# design.net
KiCad netlist of a schematic drawn in Altium Designer
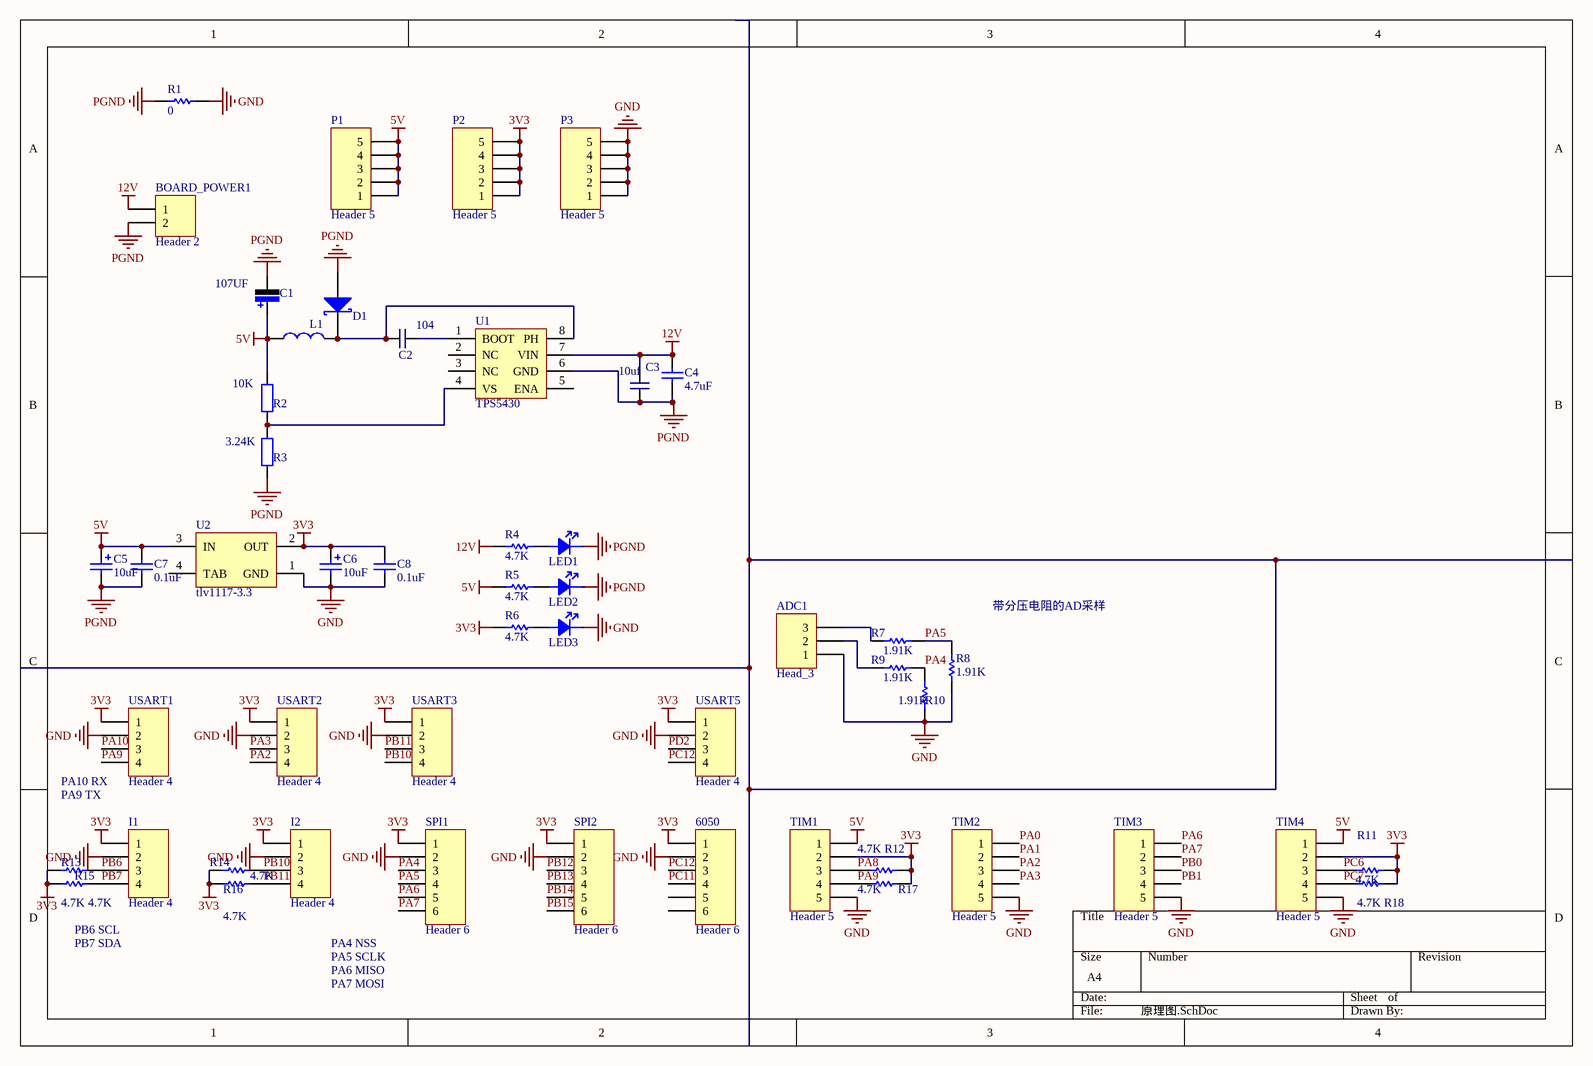
[diagram p0: 原理图.SchDoc]

(export (version "E")
  (design (tool "Eeschema 10.0.6"))
  (components
    (comp (ref "6050")
      (value "Header 6")
      (footprint "HDR1X6- duplicate")
      (description "接插件")
      (fields (field (name "PUBLISHER") "Altium Limited"))
      (libsource (lib "MySchlib") (part "Header 6"))
    )
    (comp (ref "ADC1") (value "Head_3") (footprint "HDR1X3") (libsource (lib "MySchlib") (part "Head_3")))
    (comp (ref "BOARD_POWER1")
      (value "Header 2")
      (footprint "Green_2P")
      (description "Header, 2-Pin")
      (fields (field (name "PUBLISHER") "Altium Limited"))
      (libsource (lib "K60-mainboard-v3.1") (part "Header 2"))
    )
    (comp (ref "C1")
      (value "107UF")
      (footprint "6032C  TA")
      (description "钽电容")
      (libsource (lib "MySchlib") (part "Cap_2"))
    )
    (comp (ref "C2") (value "104") (footprint "0603- C") (libsource (lib "MySchlib") (part "Cap")))
    (comp (ref "C3") (value "10uf") (footprint "0805C") (libsource (lib "MySchlib") (part "Cap")))
    (comp (ref "C4")
      (value "4.7uF")
      (footprint "CAP-MLCC-0603")
      (description "Capacitor")
      (fields (field (name "Comment") "Cap") (field (name "PUBLISHER") "Altium Limited"))
      (libsource (lib "K60-mainboard-v3.1") (part "Cap"))
    )
    (comp (ref "C5")
      (value "10uF")
      (footprint "6032C")
      (description "Polarized Capacitor (Radial)")
      (fields (field (name "Comment") "Cap Pol1") (field (name "PUBLISHER") "Altium Limited"))
      (libsource (lib "K60-mainboard-v3.1") (part "Cap Pol1"))
    )
    (comp (ref "C6")
      (value "10uF")
      (footprint "6032C")
      (description "Polarized Capacitor (Radial)")
      (fields (field (name "Comment") "Cap Pol1") (field (name "PUBLISHER") "Altium Limited"))
      (libsource (lib "K60-mainboard-v3.1") (part "Cap Pol1"))
    )
    (comp (ref "C7")
      (value "0.1uF")
      (footprint "CAP-MLCC-0603")
      (description "Capacitor")
      (fields (field (name "Comment") "Cap") (field (name "PUBLISHER") "Altium Limited"))
      (libsource (lib "K60-mainboard-v3.1") (part "Cap"))
    )
    (comp (ref "C8")
      (value "0.1uF")
      (footprint "CAP-MLCC-0603")
      (description "Capacitor")
      (fields (field (name "Comment") "Cap") (field (name "PUBLISHER") "Altium Limited"))
      (libsource (lib "K60-mainboard-v3.1") (part "Cap"))
    )
    (comp (ref "D1") (value "D") (footprint "D RS1M") (libsource (lib "MySchlib") (part "D")))
    (comp (ref "I1")
      (value "Header 4")
      (footprint "HDR1X4")
      (description "Header, 4-Pin")
      (fields (field (name "PUBLISHER") "Altium Limited"))
      (libsource (lib "K60-mainboard-v3.1") (part "Header 4"))
    )
    (comp (ref "I2")
      (value "Header 4")
      (footprint "HDR1X4")
      (description "Header, 4-Pin")
      (fields (field (name "PUBLISHER") "Altium Limited"))
      (libsource (lib "K60-mainboard-v3.1") (part "Header 4"))
    )
    (comp (ref "L1")
      (value "L")
      (footprint "CD_54")
      (description "电感")
      (libsource (lib "MySchlib") (part "L"))
    )
    (comp (ref "LED1")
      (value "lED")
      (footprint "0805D")
      (description "LED")
      (libsource (lib "K60-mainboard-v3.1") (part "00-D-LED"))
    )
    (comp (ref "LED2")
      (value "lED")
      (footprint "0805D")
      (description "LED")
      (libsource (lib "K60-mainboard-v3.1") (part "00-D-LED"))
    )
    (comp (ref "LED3")
      (value "lED")
      (footprint "0805D")
      (description "LED")
      (libsource (lib "K60-mainboard-v3.1") (part "00-D-LED"))
    )
    (comp (ref "P1")
      (value "Header 5")
      (footprint "HDR1X5")
      (description "Header, 5-Pin")
      (fields (field (name "PUBLISHER") "Altium Limited"))
      (libsource (lib "K60-mainboard-v3.1") (part "Header 5"))
    )
    (comp (ref "P2")
      (value "Header 5")
      (footprint "HDR1X5")
      (description "Header, 5-Pin")
      (fields (field (name "PUBLISHER") "Altium Limited"))
      (libsource (lib "K60-mainboard-v3.1") (part "Header 5"))
    )
    (comp (ref "P3")
      (value "Header 5")
      (footprint "HDR1X5")
      (description "Header, 5-Pin")
      (fields (field (name "PUBLISHER") "Altium Limited"))
      (libsource (lib "K60-mainboard-v3.1") (part "Header 5"))
    )
    (comp (ref "R1")
      (value "0")
      (footprint "RES-0603")
      (description "Resistor")
      (fields (field (name "Comment") "Res1") (field (name "PUBLISHER") "Altium Limited"))
      (libsource (lib "K60-mainboard-v3.1") (part "Res1"))
    )
    (comp (ref "R2") (value "10K") (footprint "0603-R") (libsource (lib "MySchlib") (part "R")))
    (comp (ref "R3") (value "3.24K") (footprint "0603-R") (libsource (lib "") (part "R_1")))
    (comp (ref "R4")
      (value "4.7K")
      (footprint "RES-0603")
      (description "Resistor")
      (fields (field (name "Comment") "Res1") (field (name "PUBLISHER") "Altium Limited"))
      (libsource (lib "K60-mainboard-v3.1") (part "Res1"))
    )
    (comp (ref "R5")
      (value "4.7K")
      (footprint "RES-0603")
      (description "Resistor")
      (fields (field (name "Comment") "Res1") (field (name "PUBLISHER") "Altium Limited"))
      (libsource (lib "K60-mainboard-v3.1") (part "Res1"))
    )
    (comp (ref "R6")
      (value "4.7K")
      (footprint "RES-0603")
      (description "Resistor")
      (fields (field (name "Comment") "Res1") (field (name "PUBLISHER") "Altium Limited"))
      (libsource (lib "K60-mainboard-v3.1") (part "Res1"))
    )
    (comp (ref "R7")
      (value "1.91K")
      (footprint "RES-0603")
      (description "Resistor")
      (fields (field (name "Comment") "Res1") (field (name "PUBLISHER") "Altium Limited"))
      (libsource (lib "K60-mainboard-v3.1") (part "Res1"))
    )
    (comp (ref "R8")
      (value "1.91K")
      (footprint "RES-0603")
      (description "Resistor")
      (fields (field (name "Comment") "Res1") (field (name "PUBLISHER") "Altium Limited"))
      (libsource (lib "K60-mainboard-v3.1") (part "Res1"))
    )
    (comp (ref "R9")
      (value "1.91K")
      (footprint "RES-0603")
      (description "Resistor")
      (fields (field (name "Comment") "Res1") (field (name "PUBLISHER") "Altium Limited"))
      (libsource (lib "K60-mainboard-v3.1") (part "Res1"))
    )
    (comp (ref "R10")
      (value "1.91K")
      (footprint "RES-0603")
      (description "Resistor")
      (fields (field (name "Comment") "Res1") (field (name "PUBLISHER") "Altium Limited"))
      (libsource (lib "K60-mainboard-v3.1") (part "Res1"))
    )
    (comp (ref "R11")
      (value "4.7K")
      (footprint "RES-0603")
      (description "Resistor")
      (fields (field (name "Comment") "Res1") (field (name "PUBLISHER") "Altium Limited"))
      (libsource (lib "K60-mainboard-v3.1") (part "Res1"))
    )
    (comp (ref "R12")
      (value "4.7K")
      (footprint "RES-0603")
      (description "Resistor")
      (fields (field (name "Comment") "Res1") (field (name "PUBLISHER") "Altium Limited"))
      (libsource (lib "K60-mainboard-v3.1") (part "Res1"))
    )
    (comp (ref "R13")
      (value "4.7K")
      (footprint "RES-0603")
      (description "Resistor")
      (fields (field (name "Comment") "Res1") (field (name "PUBLISHER") "Altium Limited"))
      (libsource (lib "K60-mainboard-v3.1") (part "Res1"))
    )
    (comp (ref "R14")
      (value "4.7K")
      (footprint "RES-0603")
      (description "Resistor")
      (fields (field (name "Comment") "Res1") (field (name "PUBLISHER") "Altium Limited"))
      (libsource (lib "K60-mainboard-v3.1") (part "Res1"))
    )
    (comp (ref "R15")
      (value "4.7K")
      (footprint "RES-0603")
      (description "Resistor")
      (fields (field (name "Comment") "Res1") (field (name "PUBLISHER") "Altium Limited"))
      (libsource (lib "K60-mainboard-v3.1") (part "Res1"))
    )
    (comp (ref "R16")
      (value "4.7K")
      (footprint "RES-0603")
      (description "Resistor")
      (fields (field (name "Comment") "Res1") (field (name "PUBLISHER") "Altium Limited"))
      (libsource (lib "K60-mainboard-v3.1") (part "Res1"))
    )
    (comp (ref "R17")
      (value "4.7K")
      (footprint "RES-0603")
      (description "Resistor")
      (fields (field (name "Comment") "Res1") (field (name "PUBLISHER") "Altium Limited"))
      (libsource (lib "K60-mainboard-v3.1") (part "Res1"))
    )
    (comp (ref "R18")
      (value "4.7K")
      (footprint "RES-0603")
      (description "Resistor")
      (fields (field (name "Comment") "Res1") (field (name "PUBLISHER") "Altium Limited"))
      (libsource (lib "K60-mainboard-v3.1") (part "Res1"))
    )
    (comp (ref "SPI1")
      (value "Header 6")
      (footprint "HDR1X6")
      (description "Header, 6-Pin")
      (fields (field (name "PUBLISHER") "Altium Limited"))
      (libsource (lib "K60-mainboard-v3.1") (part "Header 6"))
    )
    (comp (ref "SPI2")
      (value "Header 6")
      (footprint "HDR1X6")
      (description "Header, 6-Pin")
      (fields (field (name "PUBLISHER") "Altium Limited"))
      (libsource (lib "K60-mainboard-v3.1") (part "Header 6"))
    )
    (comp (ref "TIM1")
      (value "Header 5")
      (footprint "HDR1X5")
      (description "Header, 5-Pin")
      (fields (field (name "PUBLISHER") "Altium Limited"))
      (libsource (lib "") (part "Header 5_1"))
    )
    (comp (ref "TIM2")
      (value "Header 5")
      (footprint "HDR1X5")
      (description "Header, 5-Pin")
      (fields (field (name "PUBLISHER") "Altium Limited"))
      (libsource (lib "") (part "Header 5_1"))
    )
    (comp (ref "TIM3")
      (value "Header 5")
      (footprint "HDR1X5")
      (description "Header, 5-Pin")
      (fields (field (name "PUBLISHER") "Altium Limited"))
      (libsource (lib "") (part "Header 5_1"))
    )
    (comp (ref "TIM4")
      (value "Header 5")
      (footprint "HDR1X5")
      (description "Header, 5-Pin")
      (fields (field (name "PUBLISHER") "Altium Limited"))
      (libsource (lib "") (part "Header 5_1"))
    )
    (comp (ref "U1") (value "TPS5430") (footprint "SOIC-8piN") (libsource (lib "MySchlib") (part "TPS5430")))
    (comp (ref "U2")
      (value "tlv1117-3.3")
      (footprint "LM1117")
      (description "800mA Low-Dropout Linear Regulator")
      (fields
        (field (name "PARTNUMBER") "LM1117IMP-5.0")
        (field (name "MANUFACTURER") "National Semiconductor")
        (field (name "PUBLISHER") "Altium Limited")
      )
      (libsource (lib "K60-mainboard-v3.1") (part "LM1117IMP-5.0"))
    )
    (comp (ref "USART1")
      (value "Header 4")
      (footprint "HDR1X4")
      (description "Header, 4-Pin")
      (fields (field (name "PUBLISHER") "Altium Limited"))
      (libsource (lib "K60-mainboard-v3.1") (part "Header 4"))
    )
    (comp (ref "USART2")
      (value "Header 4")
      (footprint "HDR1X4")
      (description "Header, 4-Pin")
      (fields (field (name "PUBLISHER") "Altium Limited"))
      (libsource (lib "K60-mainboard-v3.1") (part "Header 4"))
    )
    (comp (ref "USART3")
      (value "Header 4")
      (footprint "HDR1X4")
      (description "Header, 4-Pin")
      (fields (field (name "PUBLISHER") "Altium Limited"))
      (libsource (lib "K60-mainboard-v3.1") (part "Header 4"))
    )
    (comp (ref "USART5")
      (value "Header 4")
      (footprint "HDR1X4")
      (description "Header, 4-Pin")
      (fields (field (name "PUBLISHER") "Altium Limited"))
      (libsource (lib "K60-mainboard-v3.1") (part "Header 4"))
    )
  )
  (nets
    (net (code "1") (name "/PA0") (class "Default")
      (node (ref "TIM2") (pin "1") (pinfunction "1_1") (pintype "passive"))
    )
    (net (code "2") (name "/PA1") (class "Default")
      (node (ref "TIM2") (pin "2") (pinfunction "2_2") (pintype "passive"))
    )
    (net (code "3") (name "/PA2") (class "Default")
      (node (ref "TIM2") (pin "3") (pinfunction "3_3") (pintype "passive"))
      (node (ref "USART2") (pin "4") (pinfunction "4_4") (pintype "passive"))
    )
    (net (code "4") (name "/PA3") (class "Default")
      (node (ref "TIM2") (pin "4") (pinfunction "4_4") (pintype "passive"))
      (node (ref "USART2") (pin "3") (pinfunction "3_3") (pintype "passive"))
    )
    (net (code "5") (name "/PA4") (class "Default")
      (node (ref "R10") (pin "1") (pinfunction "1_1") (pintype "passive"))
      (node (ref "R9") (pin "1") (pinfunction "1_1") (pintype "passive"))
      (node (ref "SPI1") (pin "3") (pinfunction "3_3") (pintype "passive"))
    )
    (net (code "6") (name "/PA5") (class "Default")
      (node (ref "R7") (pin "1") (pinfunction "1_1") (pintype "passive"))
      (node (ref "R8") (pin "1") (pinfunction "1_1") (pintype "passive"))
      (node (ref "SPI1") (pin "4") (pinfunction "4_4") (pintype "passive"))
    )
    (net (code "7") (name "/PA6") (class "Default")
      (node (ref "SPI1") (pin "5") (pinfunction "5_5") (pintype "passive"))
      (node (ref "TIM3") (pin "1") (pinfunction "1_1") (pintype "passive"))
    )
    (net (code "8") (name "/PA7") (class "Default")
      (node (ref "SPI1") (pin "6") (pinfunction "6_6") (pintype "passive"))
      (node (ref "TIM3") (pin "2") (pinfunction "2_2") (pintype "passive"))
    )
    (net (code "9") (name "/PA8") (class "Default")
      (node (ref "R12") (pin "2") (pinfunction "2_2") (pintype "passive"))
      (node (ref "TIM1") (pin "3") (pinfunction "3_3") (pintype "passive"))
    )
    (net (code "10") (name "/PA9") (class "Default")
      (node (ref "R17") (pin "2") (pinfunction "2_2") (pintype "passive"))
      (node (ref "TIM1") (pin "4") (pinfunction "4_4") (pintype "passive"))
      (node (ref "USART1") (pin "4") (pinfunction "4_4") (pintype "passive"))
    )
    (net (code "11") (name "/PA10") (class "Default")
      (node (ref "USART1") (pin "3") (pinfunction "3_3") (pintype "passive"))
    )
    (net (code "12") (name "/PB0") (class "Default")
      (node (ref "TIM3") (pin "3") (pinfunction "3_3") (pintype "passive"))
    )
    (net (code "13") (name "/PB1") (class "Default")
      (node (ref "TIM3") (pin "4") (pinfunction "4_4") (pintype "passive"))
    )
    (net (code "14") (name "/PB6") (class "Default")
      (node (ref "I1") (pin "3") (pinfunction "3_3") (pintype "passive"))
      (node (ref "R13") (pin "1") (pinfunction "1_1") (pintype "passive"))
    )
    (net (code "15") (name "/PB7") (class "Default")
      (node (ref "I1") (pin "4") (pinfunction "4_4") (pintype "passive"))
      (node (ref "R15") (pin "1") (pinfunction "1_1") (pintype "passive"))
    )
    (net (code "16") (name "/PB10") (class "Default")
      (node (ref "I2") (pin "3") (pinfunction "3_3") (pintype "passive"))
      (node (ref "R14") (pin "1") (pinfunction "1_1") (pintype "passive"))
      (node (ref "USART3") (pin "4") (pinfunction "4_4") (pintype "passive"))
    )
    (net (code "17") (name "/PB11") (class "Default")
      (node (ref "I2") (pin "4") (pinfunction "4_4") (pintype "passive"))
      (node (ref "R16") (pin "1") (pinfunction "1_1") (pintype "passive"))
      (node (ref "USART3") (pin "3") (pinfunction "3_3") (pintype "passive"))
    )
    (net (code "18") (name "/PB12") (class "Default")
      (node (ref "SPI2") (pin "3") (pinfunction "3_3") (pintype "passive"))
    )
    (net (code "19") (name "/PB13") (class "Default")
      (node (ref "SPI2") (pin "4") (pinfunction "4_4") (pintype "passive"))
    )
    (net (code "20") (name "/PB14") (class "Default")
      (node (ref "SPI2") (pin "5") (pinfunction "5_5") (pintype "passive"))
    )
    (net (code "21") (name "/PB15") (class "Default")
      (node (ref "SPI2") (pin "6") (pinfunction "6_6") (pintype "passive"))
    )
    (net (code "22") (name "/PC6") (class "Default")
      (node (ref "R11") (pin "2") (pinfunction "2_2") (pintype "passive"))
      (node (ref "TIM4") (pin "3") (pinfunction "3_3") (pintype "passive"))
    )
    (net (code "23") (name "/PC7") (class "Default")
      (node (ref "R18") (pin "2") (pinfunction "2_2") (pintype "passive"))
      (node (ref "TIM4") (pin "4") (pinfunction "4_4") (pintype "passive"))
    )
    (net (code "24") (name "/PC11") (class "Default")
      (node (ref "6050") (pin "4") (pinfunction "4_4") (pintype "passive"))
    )
    (net (code "25") (name "/PC12") (class "Default")
      (node (ref "6050") (pin "3") (pinfunction "3_3") (pintype "passive"))
      (node (ref "USART5") (pin "4") (pinfunction "4_4") (pintype "passive"))
    )
    (net (code "26") (name "/PD2") (class "Default")
      (node (ref "USART5") (pin "3") (pinfunction "3_3") (pintype "passive"))
    )
    (net (code "27") (name "3V3") (class "Default")
      (node (ref "6050") (pin "1") (pinfunction "1_1") (pintype "passive"))
      (node (ref "C6") (pin "1") (pinfunction "1_1") (pintype "passive"))
      (node (ref "C8") (pin "2") (pinfunction "2_2") (pintype "passive"))
      (node (ref "I1") (pin "1") (pinfunction "1_1") (pintype "passive"))
      (node (ref "I2") (pin "1") (pinfunction "1_1") (pintype "passive"))
      (node (ref "P2") (pin "1") (pinfunction "1_1") (pintype "passive"))
      (node (ref "P2") (pin "2") (pinfunction "2_2") (pintype "passive"))
      (node (ref "P2") (pin "3") (pinfunction "3_3") (pintype "passive"))
      (node (ref "P2") (pin "4") (pinfunction "4_4") (pintype "passive"))
      (node (ref "P2") (pin "5") (pinfunction "5_5") (pintype "passive"))
      (node (ref "R11") (pin "1") (pinfunction "1_1") (pintype "passive"))
      (node (ref "R12") (pin "1") (pinfunction "1_1") (pintype "passive"))
      (node (ref "R13") (pin "2") (pinfunction "2_2") (pintype "passive"))
      (node (ref "R14") (pin "2") (pinfunction "2_2") (pintype "passive"))
      (node (ref "R15") (pin "2") (pinfunction "2_2") (pintype "passive"))
      (node (ref "R16") (pin "2") (pinfunction "2_2") (pintype "passive"))
      (node (ref "R17") (pin "1") (pinfunction "1_1") (pintype "passive"))
      (node (ref "R18") (pin "1") (pinfunction "1_1") (pintype "passive"))
      (node (ref "R6") (pin "2") (pinfunction "2_2") (pintype "passive"))
      (node (ref "SPI1") (pin "1") (pinfunction "1_1") (pintype "passive"))
      (node (ref "SPI2") (pin "1") (pinfunction "1_1") (pintype "passive"))
      (node (ref "TIM1") (pin "2") (pinfunction "2_2") (pintype "passive"))
      (node (ref "TIM4") (pin "2") (pinfunction "2_2") (pintype "passive"))
      (node (ref "U2") (pin "2") (pinfunction "OUT_2") (pintype "power_in"))
      (node (ref "USART1") (pin "1") (pinfunction "1_1") (pintype "passive"))
      (node (ref "USART2") (pin "1") (pinfunction "1_1") (pintype "passive"))
      (node (ref "USART3") (pin "1") (pinfunction "1_1") (pintype "passive"))
      (node (ref "USART5") (pin "1") (pinfunction "1_1") (pintype "passive"))
    )
    (net (code "28") (name "5V") (class "Default")
      (node (ref "C1") (pin "1") (pinfunction "1_1") (pintype "passive"))
      (node (ref "C5") (pin "1") (pinfunction "1_1") (pintype "passive"))
      (node (ref "C7") (pin "2") (pinfunction "2_2") (pintype "passive"))
      (node (ref "L1") (pin "2") (pintype "passive"))
      (node (ref "P1") (pin "1") (pinfunction "1_1") (pintype "passive"))
      (node (ref "P1") (pin "2") (pinfunction "2_2") (pintype "passive"))
      (node (ref "P1") (pin "3") (pinfunction "3_3") (pintype "passive"))
      (node (ref "P1") (pin "4") (pinfunction "4_4") (pintype "passive"))
      (node (ref "P1") (pin "5") (pinfunction "5_5") (pintype "passive"))
      (node (ref "R2") (pin "2") (pinfunction "2_2") (pintype "passive"))
      (node (ref "R5") (pin "2") (pinfunction "2_2") (pintype "passive"))
      (node (ref "TIM1") (pin "1") (pinfunction "1_1") (pintype "passive"))
      (node (ref "TIM4") (pin "1") (pinfunction "1_1") (pintype "passive"))
      (node (ref "U2") (pin "3") (pinfunction "IN_3") (pintype "power_in"))
    )
    (net (code "29") (name "12V") (class "Default")
      (node (ref "BOARD_POWER1") (pin "1") (pinfunction "1_1") (pintype "passive"))
      (node (ref "C3") (pin "2") (pinfunction "2_2") (pintype "passive"))
      (node (ref "C4") (pin "2") (pinfunction "2_2") (pintype "passive"))
      (node (ref "R4") (pin "2") (pinfunction "2_2") (pintype "passive"))
      (node (ref "U1") (pin "7") (pinfunction "VIN_7") (pintype "passive"))
    )
    (net (code "30") (name "GND") (class "Default")
      (node (ref "6050") (pin "2") (pinfunction "2_2") (pintype "passive"))
      (node (ref "ADC1") (pin "1") (pinfunction "1_1") (pintype "passive"))
      (node (ref "C6") (pin "2") (pinfunction "2_2") (pintype "passive"))
      (node (ref "C8") (pin "1") (pinfunction "1_1") (pintype "passive"))
      (node (ref "I1") (pin "2") (pinfunction "2_2") (pintype "passive"))
      (node (ref "I2") (pin "2") (pinfunction "2_2") (pintype "passive"))
      (node (ref "LED3") (pin "K") (pinfunction "2_K") (pintype "passive"))
      (node (ref "P3") (pin "1") (pinfunction "1_1") (pintype "passive"))
      (node (ref "P3") (pin "2") (pinfunction "2_2") (pintype "passive"))
      (node (ref "P3") (pin "3") (pinfunction "3_3") (pintype "passive"))
      (node (ref "P3") (pin "4") (pinfunction "4_4") (pintype "passive"))
      (node (ref "P3") (pin "5") (pinfunction "5_5") (pintype "passive"))
      (node (ref "R1") (pin "2") (pinfunction "2_2") (pintype "passive"))
      (node (ref "R10") (pin "2") (pinfunction "2_2") (pintype "passive"))
      (node (ref "R8") (pin "2") (pinfunction "2_2") (pintype "passive"))
      (node (ref "SPI1") (pin "2") (pinfunction "2_2") (pintype "passive"))
      (node (ref "SPI2") (pin "2") (pinfunction "2_2") (pintype "passive"))
      (node (ref "TIM1") (pin "5") (pinfunction "5_5") (pintype "passive"))
      (node (ref "TIM2") (pin "5") (pinfunction "5_5") (pintype "passive"))
      (node (ref "TIM3") (pin "5") (pinfunction "5_5") (pintype "passive"))
      (node (ref "TIM4") (pin "5") (pinfunction "5_5") (pintype "passive"))
      (node (ref "U2") (pin "1") (pinfunction "GND_1") (pintype "power_in"))
      (node (ref "USART1") (pin "2") (pinfunction "2_2") (pintype "passive"))
      (node (ref "USART2") (pin "2") (pinfunction "2_2") (pintype "passive"))
      (node (ref "USART3") (pin "2") (pinfunction "2_2") (pintype "passive"))
      (node (ref "USART5") (pin "2") (pinfunction "2_2") (pintype "passive"))
    )
    (net (code "31") (name "Net-(ADC1-Pad2)") (class "Default")
      (node (ref "ADC1") (pin "2") (pinfunction "2_2") (pintype "passive"))
      (node (ref "R9") (pin "2") (pinfunction "2_2") (pintype "passive"))
    )
    (net (code "32") (name "Net-(ADC1-Pad3)") (class "Default")
      (node (ref "ADC1") (pin "3") (pinfunction "3_3") (pintype "passive"))
      (node (ref "R7") (pin "2") (pinfunction "2_2") (pintype "passive"))
    )
    (net (code "33") (name "Net-(LED1-1)") (class "Default")
      (node (ref "LED1") (pin "A") (pinfunction "1_A") (pintype "passive"))
      (node (ref "R4") (pin "1") (pinfunction "1_1") (pintype "passive"))
    )
    (net (code "34") (name "Net-(LED2-1)") (class "Default")
      (node (ref "LED2") (pin "A") (pinfunction "1_A") (pintype "passive"))
      (node (ref "R5") (pin "1") (pinfunction "1_1") (pintype "passive"))
    )
    (net (code "35") (name "Net-(LED3-1)") (class "Default")
      (node (ref "LED3") (pin "A") (pinfunction "1_A") (pintype "passive"))
      (node (ref "R6") (pin "1") (pinfunction "1_1") (pintype "passive"))
    )
    (net (code "36") (name "Net-(U1-BOOT)") (class "Default")
      (node (ref "C2") (pin "1") (pinfunction "1_1") (pintype "passive"))
      (node (ref "U1") (pin "1") (pinfunction "BOOT_1") (pintype "passive"))
    )
    (net (code "37") (name "Net-(U1-PH)") (class "Default")
      (node (ref "C2") (pin "2") (pinfunction "2_2") (pintype "passive"))
      (node (ref "D1") (pin "K") (pinfunction "K_K") (pintype "passive"))
      (node (ref "L1") (pin "1") (pintype "passive"))
      (node (ref "U1") (pin "8") (pinfunction "PH_8") (pintype "passive"))
    )
    (net (code "38") (name "Net-(U1-VS)") (class "Default")
      (node (ref "R2") (pin "1") (pinfunction "1_1") (pintype "passive"))
      (node (ref "R3") (pin "1") (pinfunction "1_1") (pintype "passive"))
      (node (ref "U1") (pin "4") (pinfunction "VS_4") (pintype "passive"))
    )
    (net (code "39") (name "PGND") (class "Default")
      (node (ref "BOARD_POWER1") (pin "2") (pinfunction "2_2") (pintype "passive"))
      (node (ref "C1") (pin "2") (pinfunction "2_2") (pintype "passive"))
      (node (ref "C3") (pin "1") (pinfunction "1_1") (pintype "passive"))
      (node (ref "C4") (pin "1") (pinfunction "1_1") (pintype "passive"))
      (node (ref "C5") (pin "2") (pinfunction "2_2") (pintype "passive"))
      (node (ref "C7") (pin "1") (pinfunction "1_1") (pintype "passive"))
      (node (ref "D1") (pin "A") (pinfunction "A_A") (pintype "passive"))
      (node (ref "LED1") (pin "K") (pinfunction "2_K") (pintype "passive"))
      (node (ref "LED2") (pin "K") (pinfunction "2_K") (pintype "passive"))
      (node (ref "R1") (pin "1") (pinfunction "1_1") (pintype "passive"))
      (node (ref "R3") (pin "2") (pinfunction "2_2") (pintype "passive"))
      (node (ref "U1") (pin "6") (pinfunction "GND_6") (pintype "passive"))
    )
    (net (code "40") (name "unconnected-(6050-Pad5)") (class "Default")
      (node (ref "6050") (pin "5") (pinfunction "5_5") (pintype "passive"))
    )
    (net (code "41") (name "unconnected-(6050-Pad6)") (class "Default")
      (node (ref "6050") (pin "6") (pinfunction "6_6") (pintype "passive"))
    )
    (net (code "42") (name "unconnected-(U1-ENA-Pad5)") (class "Default")
      (node (ref "U1") (pin "5") (pinfunction "ENA_5") (pintype "passive"))
    )
    (net (code "43") (name "unconnected-(U1-NC-Pad2)") (class "Default")
      (node (ref "U1") (pin "2") (pinfunction "NC_2") (pintype "passive"))
    )
    (net (code "44") (name "unconnected-(U1-NC-Pad3)") (class "Default")
      (node (ref "U1") (pin "3") (pinfunction "NC_3") (pintype "passive"))
    )
    (net (code "45") (name "unconnected-(U2-TAB-Pad4)") (class "Default")
      (node (ref "U2") (pin "4") (pinfunction "TAB_4") (pintype "power_in"))
    )
  )
)
